# E17-PDU-LOAD_2.net
KiCad netlist of a schematic drawn in Altium Designer
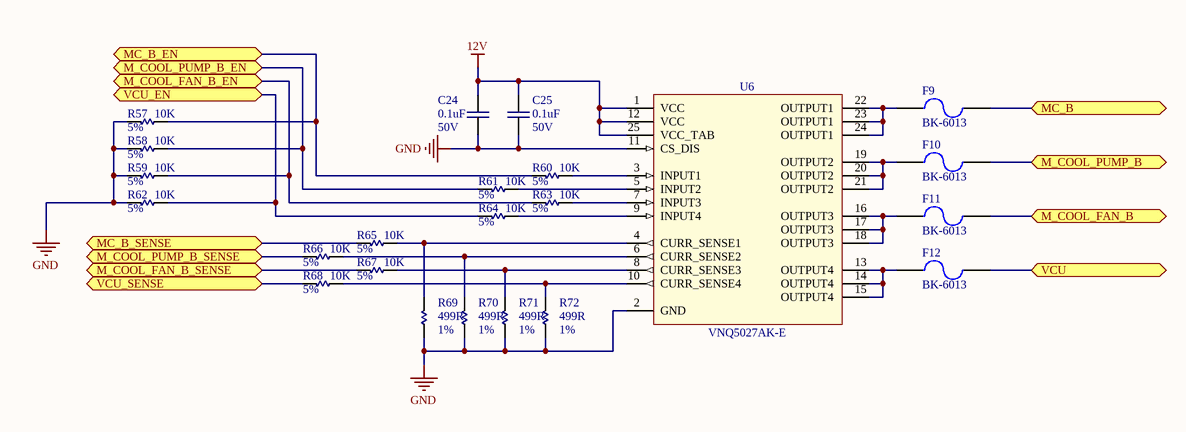
[diagram p0: E17-PDU-LOAD_2.SchDoc]

(export (version "E")
  (design (tool "Eeschema 10.0.6"))
  (components
    (comp (ref "C24")
      (value "0.1uF")
      (footprint "C0805")
      (description "Generic 0805 Capacitor")
      (fields
        (field (name "TOLERANCE") "10%")
        (field (name "VOLTAGE") "50V")
        (field (name "Comment") "C_0805_Generic")
      )
      (libsource (lib "Compiled_PDU") (part "C_0805_Generic"))
    )
    (comp (ref "C25")
      (value "0.1uF")
      (footprint "C0805")
      (description "Generic 0805 Capacitor")
      (fields
        (field (name "TOLERANCE") "10%")
        (field (name "VOLTAGE") "50V")
        (field (name "Comment") "C_0805_Generic")
      )
      (libsource (lib "Compiled_PDU") (part "C_0805_Generic"))
    )
    (comp (ref "F9")
      (value "F_BK-6013")
      (footprint "BK-6013")
      (description "FUSE HOLDER BLADE PCB")
      (fields (field (name "MFG") "MPD") (field (name "MFG_PN") "BK-6013"))
      (libsource (lib "Compiled_PDU") (part "F_BK-6013"))
    )
    (comp (ref "F10")
      (value "F_BK-6013")
      (footprint "BK-6013")
      (description "FUSE HOLDER BLADE PCB")
      (fields (field (name "MFG") "MPD") (field (name "MFG_PN") "BK-6013"))
      (libsource (lib "Compiled_PDU") (part "F_BK-6013"))
    )
    (comp (ref "F11")
      (value "F_BK-6013")
      (footprint "BK-6013")
      (description "FUSE HOLDER BLADE PCB")
      (fields (field (name "MFG") "MPD") (field (name "MFG_PN") "BK-6013"))
      (libsource (lib "Compiled_PDU") (part "F_BK-6013"))
    )
    (comp (ref "F12")
      (value "F_BK-6013")
      (footprint "BK-6013")
      (description "FUSE HOLDER BLADE PCB")
      (fields (field (name "MFG") "MPD") (field (name "MFG_PN") "BK-6013"))
      (libsource (lib "Compiled_PDU") (part "F_BK-6013"))
    )
    (comp (ref "R57")
      (value "10K")
      (footprint "R0603")
      (description "Generic 0603 Resistor")
      (fields
        (field (name "POWER") "1/10W")
        (field (name "TOLERANCE") "5%")
        (field (name "Comment") "R_0603_Generic")
      )
      (libsource (lib "Compiled_PDU") (part "R_0603_Generic"))
    )
    (comp (ref "R58")
      (value "10K")
      (footprint "R0603")
      (description "Generic 0603 Resistor")
      (fields
        (field (name "POWER") "1/10W")
        (field (name "TOLERANCE") "5%")
        (field (name "Comment") "R_0603_Generic")
      )
      (libsource (lib "Compiled_PDU") (part "R_0603_Generic"))
    )
    (comp (ref "R59")
      (value "10K")
      (footprint "R0603")
      (description "Generic 0603 Resistor")
      (fields
        (field (name "POWER") "1/10W")
        (field (name "TOLERANCE") "5%")
        (field (name "Comment") "R_0603_Generic")
      )
      (libsource (lib "Compiled_PDU") (part "R_0603_Generic"))
    )
    (comp (ref "R60")
      (value "10K")
      (footprint "R0603")
      (description "Generic 0603 Resistor")
      (fields
        (field (name "POWER") "1/10W")
        (field (name "TOLERANCE") "5%")
        (field (name "Comment") "R_0603_Generic")
      )
      (libsource (lib "Compiled_PDU") (part "R_0603_Generic"))
    )
    (comp (ref "R61")
      (value "10K")
      (footprint "R0603")
      (description "Generic 0603 Resistor")
      (fields
        (field (name "POWER") "1/10W")
        (field (name "TOLERANCE") "5%")
        (field (name "Comment") "R_0603_Generic")
      )
      (libsource (lib "Compiled_PDU") (part "R_0603_Generic"))
    )
    (comp (ref "R62")
      (value "10K")
      (footprint "R0603")
      (description "Generic 0603 Resistor")
      (fields
        (field (name "POWER") "1/10W")
        (field (name "TOLERANCE") "5%")
        (field (name "Comment") "R_0603_Generic")
      )
      (libsource (lib "Compiled_PDU") (part "R_0603_Generic"))
    )
    (comp (ref "R63")
      (value "10K")
      (footprint "R0603")
      (description "Generic 0603 Resistor")
      (fields
        (field (name "POWER") "1/10W")
        (field (name "TOLERANCE") "5%")
        (field (name "Comment") "R_0603_Generic")
      )
      (libsource (lib "Compiled_PDU") (part "R_0603_Generic"))
    )
    (comp (ref "R64")
      (value "10K")
      (footprint "R0603")
      (description "Generic 0603 Resistor")
      (fields
        (field (name "POWER") "1/10W")
        (field (name "TOLERANCE") "5%")
        (field (name "Comment") "R_0603_Generic")
      )
      (libsource (lib "Compiled_PDU") (part "R_0603_Generic"))
    )
    (comp (ref "R65")
      (value "10K")
      (footprint "R0603")
      (description "Generic 0603 Resistor")
      (fields
        (field (name "POWER") "1/10W")
        (field (name "TOLERANCE") "5%")
        (field (name "Comment") "R_0603_Generic")
      )
      (libsource (lib "Compiled_PDU") (part "R_0603_Generic"))
    )
    (comp (ref "R66")
      (value "10K")
      (footprint "R0603")
      (description "Generic 0603 Resistor")
      (fields
        (field (name "POWER") "1/10W")
        (field (name "TOLERANCE") "5%")
        (field (name "Comment") "R_0603_Generic")
      )
      (libsource (lib "Compiled_PDU") (part "R_0603_Generic"))
    )
    (comp (ref "R67")
      (value "10K")
      (footprint "R0603")
      (description "Generic 0603 Resistor")
      (fields
        (field (name "POWER") "1/10W")
        (field (name "TOLERANCE") "5%")
        (field (name "Comment") "R_0603_Generic")
      )
      (libsource (lib "Compiled_PDU") (part "R_0603_Generic"))
    )
    (comp (ref "R68")
      (value "10K")
      (footprint "R0603")
      (description "Generic 0603 Resistor")
      (fields
        (field (name "POWER") "1/10W")
        (field (name "TOLERANCE") "5%")
        (field (name "Comment") "R_0603_Generic")
      )
      (libsource (lib "Compiled_PDU") (part "R_0603_Generic"))
    )
    (comp (ref "R69")
      (value "499R")
      (footprint "R0603")
      (description "Generic 0603 Resistor")
      (fields
        (field (name "POWER") "1/8W")
        (field (name "TOLERANCE") "1%")
        (field (name "Comment") "R_0603_Generic")
      )
      (libsource (lib "Compiled_PDU") (part "R_0603_Generic"))
    )
    (comp (ref "R70")
      (value "499R")
      (footprint "R0603")
      (description "Generic 0603 Resistor")
      (fields
        (field (name "POWER") "1/8W")
        (field (name "TOLERANCE") "1%")
        (field (name "Comment") "R_0603_Generic")
      )
      (libsource (lib "Compiled_PDU") (part "R_0603_Generic"))
    )
    (comp (ref "R71")
      (value "499R")
      (footprint "R0603")
      (description "Generic 0603 Resistor")
      (fields
        (field (name "POWER") "1/8W")
        (field (name "TOLERANCE") "1%")
        (field (name "Comment") "R_0603_Generic")
      )
      (libsource (lib "Compiled_PDU") (part "R_0603_Generic"))
    )
    (comp (ref "R72")
      (value "499R")
      (footprint "R0603")
      (description "Generic 0603 Resistor")
      (fields
        (field (name "POWER") "1/8W")
        (field (name "TOLERANCE") "1%")
        (field (name "Comment") "R_0603_Generic")
      )
      (libsource (lib "Compiled_PDU") (part "R_0603_Generic"))
    )
    (comp (ref "U6")
      (value "U_VNQ5027AK-E")
      (footprint "PowerSSO-24")
      (description "LOAD CHANNEL HIGH SIDE 42A 4 Channel")
      (fields (field (name "MFG") "STmicroelectronics") (field (name "MFG_PN") "VNQ5027AK-E"))
      (libsource (lib "Compiled_PDU") (part "U_VNQ5027AK-E"))
    )
  )
  (nets
    (net (code "1") (name "/MC_B") (class "Default")
      (node (ref "F9") (pin "2") (pinfunction "2_2") (pintype "passive"))
    )
    (net (code "2") (name "/MC_B_EN") (class "Default")
      (node (ref "R57") (pin "2") (pinfunction "2_2") (pintype "passive"))
      (node (ref "R60") (pin "1") (pinfunction "1_1") (pintype "passive"))
    )
    (net (code "3") (name "/MC_B_SENSE") (class "Default")
      (node (ref "R65") (pin "1") (pinfunction "1_1") (pintype "passive"))
    )
    (net (code "4") (name "/M_COOL_FAN_B") (class "Default")
      (node (ref "F11") (pin "2") (pinfunction "2_2") (pintype "passive"))
    )
    (net (code "5") (name "/M_COOL_FAN_B_EN") (class "Default")
      (node (ref "R59") (pin "2") (pinfunction "2_2") (pintype "passive"))
      (node (ref "R63") (pin "1") (pinfunction "1_1") (pintype "passive"))
    )
    (net (code "6") (name "/M_COOL_FAN_B_SENSE") (class "Default")
      (node (ref "R67") (pin "1") (pinfunction "1_1") (pintype "passive"))
    )
    (net (code "7") (name "/M_COOL_PUMP_B") (class "Default")
      (node (ref "F10") (pin "2") (pinfunction "2_2") (pintype "passive"))
    )
    (net (code "8") (name "/M_COOL_PUMP_B_EN") (class "Default")
      (node (ref "R58") (pin "2") (pinfunction "2_2") (pintype "passive"))
      (node (ref "R61") (pin "1") (pinfunction "1_1") (pintype "passive"))
    )
    (net (code "9") (name "/M_COOL_PUMP_B_SENSE") (class "Default")
      (node (ref "R66") (pin "1") (pinfunction "1_1") (pintype "passive"))
    )
    (net (code "10") (name "/VCU") (class "Default")
      (node (ref "F12") (pin "2") (pinfunction "2_2") (pintype "passive"))
    )
    (net (code "11") (name "/VCU_EN") (class "Default")
      (node (ref "R62") (pin "2") (pinfunction "2_2") (pintype "passive"))
      (node (ref "R64") (pin "1") (pinfunction "1_1") (pintype "passive"))
    )
    (net (code "12") (name "/VCU_SENSE") (class "Default")
      (node (ref "R68") (pin "1") (pinfunction "1_1") (pintype "passive"))
    )
    (net (code "13") (name "12V") (class "Default")
      (node (ref "C24") (pin "1") (pinfunction "EGND_1") (pintype "passive"))
      (node (ref "C25") (pin "1") (pinfunction "EGND_1") (pintype "passive"))
      (node (ref "U6") (pin "1") (pinfunction "VCC_1") (pintype "power_in"))
      (node (ref "U6") (pin "12") (pinfunction "VCC_12") (pintype "power_in"))
      (node (ref "U6") (pin "25") (pinfunction "VCC_TAB_25") (pintype "power_in"))
    )
    (net (code "14") (name "GND") (class "Default")
      (node (ref "C24") (pin "2") (pinfunction "2_2") (pintype "passive"))
      (node (ref "C25") (pin "2") (pinfunction "2_2") (pintype "passive"))
      (node (ref "R57") (pin "1") (pinfunction "1_1") (pintype "passive"))
      (node (ref "R58") (pin "1") (pinfunction "1_1") (pintype "passive"))
      (node (ref "R59") (pin "1") (pinfunction "1_1") (pintype "passive"))
      (node (ref "R62") (pin "1") (pinfunction "1_1") (pintype "passive"))
      (node (ref "R69") (pin "2") (pinfunction "2_2") (pintype "passive"))
      (node (ref "R70") (pin "2") (pinfunction "2_2") (pintype "passive"))
      (node (ref "R71") (pin "2") (pinfunction "2_2") (pintype "passive"))
      (node (ref "R72") (pin "2") (pinfunction "2_2") (pintype "passive"))
      (node (ref "U6") (pin "11") (pinfunction "CS_DIS_11") (pintype "input"))
      (node (ref "U6") (pin "2") (pinfunction "GND_2") (pintype "power_in"))
    )
    (net (code "15") (name "Net-(F9-Pad1)") (class "Default")
      (node (ref "F9") (pin "1") (pinfunction "1_1") (pintype "passive"))
      (node (ref "U6") (pin "22") (pinfunction "OUTPUT1_22") (pintype "power_in"))
      (node (ref "U6") (pin "23") (pinfunction "OUTPUT1_23") (pintype "power_in"))
      (node (ref "U6") (pin "24") (pinfunction "OUTPUT1_24") (pintype "power_in"))
    )
    (net (code "16") (name "Net-(F10-Pad1)") (class "Default")
      (node (ref "F10") (pin "1") (pinfunction "1_1") (pintype "passive"))
      (node (ref "U6") (pin "19") (pinfunction "OUTPUT2_19") (pintype "power_in"))
      (node (ref "U6") (pin "20") (pinfunction "OUTPUT2_20") (pintype "power_in"))
      (node (ref "U6") (pin "21") (pinfunction "OUTPUT2_21") (pintype "power_in"))
    )
    (net (code "17") (name "Net-(F11-Pad1)") (class "Default")
      (node (ref "F11") (pin "1") (pinfunction "1_1") (pintype "passive"))
      (node (ref "U6") (pin "16") (pinfunction "OUTPUT3_16") (pintype "power_in"))
      (node (ref "U6") (pin "17") (pinfunction "OUTPUT3_17") (pintype "power_in"))
      (node (ref "U6") (pin "18") (pinfunction "OUTPUT3_18") (pintype "power_in"))
    )
    (net (code "18") (name "Net-(F12-Pad1)") (class "Default")
      (node (ref "F12") (pin "1") (pinfunction "1_1") (pintype "passive"))
      (node (ref "U6") (pin "13") (pinfunction "OUTPUT4_13") (pintype "power_in"))
      (node (ref "U6") (pin "14") (pinfunction "OUTPUT4_14") (pintype "power_in"))
      (node (ref "U6") (pin "15") (pinfunction "OUTPUT4_15") (pintype "power_in"))
    )
    (net (code "19") (name "Net-(U6-CURR_SENSE1)") (class "Default")
      (node (ref "R65") (pin "2") (pinfunction "2_2") (pintype "passive"))
      (node (ref "R69") (pin "1") (pinfunction "1_1") (pintype "passive"))
      (node (ref "U6") (pin "4") (pinfunction "CURR_SENSE1_4") (pintype "output"))
    )
    (net (code "20") (name "Net-(U6-CURR_SENSE2)") (class "Default")
      (node (ref "R66") (pin "2") (pinfunction "2_2") (pintype "passive"))
      (node (ref "R70") (pin "1") (pinfunction "1_1") (pintype "passive"))
      (node (ref "U6") (pin "6") (pinfunction "CURR_SENSE2_6") (pintype "output"))
    )
    (net (code "21") (name "Net-(U6-CURR_SENSE3)") (class "Default")
      (node (ref "R67") (pin "2") (pinfunction "2_2") (pintype "passive"))
      (node (ref "R71") (pin "1") (pinfunction "1_1") (pintype "passive"))
      (node (ref "U6") (pin "8") (pinfunction "CURR_SENSE3_8") (pintype "output"))
    )
    (net (code "22") (name "Net-(U6-CURR_SENSE4)") (class "Default")
      (node (ref "R68") (pin "2") (pinfunction "2_2") (pintype "passive"))
      (node (ref "R72") (pin "1") (pinfunction "1_1") (pintype "passive"))
      (node (ref "U6") (pin "10") (pinfunction "CURR_SENSE4_10") (pintype "output"))
    )
    (net (code "23") (name "Net-(U6-INPUT1)") (class "Default")
      (node (ref "R60") (pin "2") (pinfunction "2_2") (pintype "passive"))
      (node (ref "U6") (pin "3") (pinfunction "INPUT1_3") (pintype "input"))
    )
    (net (code "24") (name "Net-(U6-INPUT2)") (class "Default")
      (node (ref "R61") (pin "2") (pinfunction "2_2") (pintype "passive"))
      (node (ref "U6") (pin "5") (pinfunction "INPUT2_5") (pintype "input"))
    )
    (net (code "25") (name "Net-(U6-INPUT3)") (class "Default")
      (node (ref "R63") (pin "2") (pinfunction "2_2") (pintype "passive"))
      (node (ref "U6") (pin "7") (pinfunction "INPUT3_7") (pintype "input"))
    )
    (net (code "26") (name "Net-(U6-INPUT4)") (class "Default")
      (node (ref "R64") (pin "2") (pinfunction "2_2") (pintype "passive"))
      (node (ref "U6") (pin "9") (pinfunction "INPUT4_9") (pintype "input"))
    )
  )
)
